# Robo2.net
KiCad netlist of a schematic drawn in Altium Designer
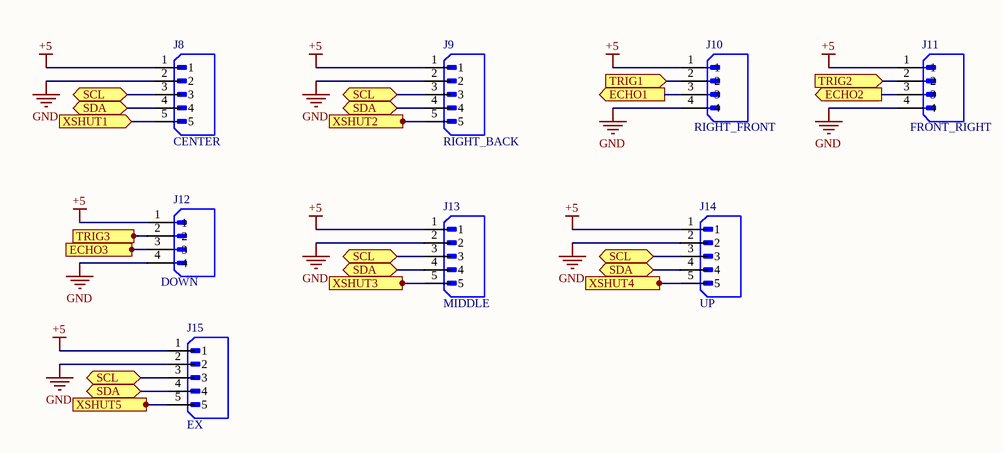
[diagram p0: Robo2.SchDoc]

(export (version "E")
  (design (tool "Eeschema 10.0.6"))
  (components
    (comp (ref "J8")
      (value "CENTER")
      (footprint "JST_B5B-XH-A(LF)(SN)")
      (description "Connector Header Through Hole 5 position 0.098 (2.50mm)")
      (fields (field (name "MF") "JST Sales America Inc.") (field (name "MP") "B5B-XH-A(LF)(SN)"))
      (libsource (lib "robo") (part "B5B-XH-A(LF)(SN)"))
    )
    (comp (ref "J9")
      (value "RIGHT_BACK")
      (footprint "JST_B5B-XH-A(LF)(SN)")
      (description "Connector Header Through Hole 5 position 0.098 (2.50mm)")
      (fields (field (name "MF") "JST Sales America Inc.") (field (name "MP") "B5B-XH-A(LF)(SN)"))
      (libsource (lib "robo") (part "B5B-XH-A(LF)(SN)"))
    )
    (comp (ref "J10")
      (value "RIGHT_FRONT")
      (footprint "JST_B4B-XH-A(LF)(SN)")
      (description "Connector Header Through Hole 4 position 0.098 (2.50mm)")
      (fields (field (name "MP") "B4B-XH-A(LF)(SN)") (field (name "MF") "JST Sales"))
      (libsource (lib "robo") (part "B4B-XH-A(LF)(SN)"))
    )
    (comp (ref "J11")
      (value "FRONT_RIGHT")
      (footprint "JST_B4B-XH-A(LF)(SN)")
      (description "Connector Header Through Hole 4 position 0.098 (2.50mm)")
      (fields (field (name "MP") "B4B-XH-A(LF)(SN)") (field (name "MF") "JST Sales"))
      (libsource (lib "robo") (part "B4B-XH-A(LF)(SN)"))
    )
    (comp (ref "J12")
      (value "DOWN")
      (footprint "JST_B4B-XH-A(LF)(SN)")
      (description "Connector Header Through Hole 4 position 0.098 (2.50mm)")
      (fields (field (name "MP") "B4B-XH-A(LF)(SN)") (field (name "MF") "JST Sales"))
      (libsource (lib "robo") (part "B4B-XH-A(LF)(SN)"))
    )
    (comp (ref "J13")
      (value "MIDDLE")
      (footprint "JST_B5B-XH-A(LF)(SN)")
      (description "Connector Header Through Hole 5 position 0.098 (2.50mm)")
      (fields (field (name "MF") "JST Sales America Inc.") (field (name "MP") "B5B-XH-A(LF)(SN)"))
      (libsource (lib "robo") (part "B5B-XH-A(LF)(SN)"))
    )
    (comp (ref "J14")
      (value "UP")
      (footprint "JST_B5B-XH-A(LF)(SN)")
      (description "Connector Header Through Hole 5 position 0.098 (2.50mm)")
      (fields (field (name "MF") "JST Sales America Inc.") (field (name "MP") "B5B-XH-A(LF)(SN)"))
      (libsource (lib "robo") (part "B5B-XH-A(LF)(SN)"))
    )
    (comp (ref "J15")
      (value "EX")
      (footprint "JST_B5B-XH-A(LF)(SN)")
      (description "Connector Header Through Hole 5 position 0.098 (2.50mm)")
      (fields (field (name "MF") "JST Sales America Inc.") (field (name "MP") "B5B-XH-A(LF)(SN)"))
      (libsource (lib "robo") (part "B5B-XH-A(LF)(SN)"))
    )
  )
  (nets
    (net (code "1") (name "+5") (class "Default")
      (node (ref "J10") (pin "1") (pinfunction "1_1") (pintype "passive"))
      (node (ref "J11") (pin "1") (pinfunction "1_1") (pintype "passive"))
      (node (ref "J12") (pin "1") (pinfunction "1_1") (pintype "passive"))
      (node (ref "J13") (pin "1") (pinfunction "1_1") (pintype "passive"))
      (node (ref "J14") (pin "1") (pinfunction "1_1") (pintype "passive"))
      (node (ref "J15") (pin "1") (pinfunction "1_1") (pintype "passive"))
      (node (ref "J8") (pin "1") (pinfunction "1_1") (pintype "passive"))
      (node (ref "J9") (pin "1") (pinfunction "1_1") (pintype "passive"))
    )
    (net (code "2") (name "/ECHO1") (class "Default")
      (node (ref "J10") (pin "3") (pinfunction "3_3") (pintype "passive"))
    )
    (net (code "3") (name "/ECHO2") (class "Default")
      (node (ref "J11") (pin "3") (pinfunction "3_3") (pintype "passive"))
    )
    (net (code "4") (name "/ECHO3") (class "Default")
      (node (ref "J12") (pin "3") (pinfunction "3_3") (pintype "passive"))
    )
    (net (code "5") (name "/SCL") (class "Default")
      (node (ref "J13") (pin "3") (pinfunction "3_3") (pintype "passive"))
      (node (ref "J14") (pin "3") (pinfunction "3_3") (pintype "passive"))
      (node (ref "J15") (pin "3") (pinfunction "3_3") (pintype "passive"))
      (node (ref "J8") (pin "3") (pinfunction "3_3") (pintype "passive"))
      (node (ref "J9") (pin "3") (pinfunction "3_3") (pintype "passive"))
    )
    (net (code "6") (name "/SDA") (class "Default")
      (node (ref "J13") (pin "4") (pinfunction "4_4") (pintype "passive"))
      (node (ref "J14") (pin "4") (pinfunction "4_4") (pintype "passive"))
      (node (ref "J15") (pin "4") (pinfunction "4_4") (pintype "passive"))
      (node (ref "J8") (pin "4") (pinfunction "4_4") (pintype "passive"))
      (node (ref "J9") (pin "4") (pinfunction "4_4") (pintype "passive"))
    )
    (net (code "7") (name "/TRIG1") (class "Default")
      (node (ref "J10") (pin "2") (pinfunction "2_2") (pintype "passive"))
    )
    (net (code "8") (name "/TRIG2") (class "Default")
      (node (ref "J11") (pin "2") (pinfunction "2_2") (pintype "passive"))
    )
    (net (code "9") (name "/TRIG3") (class "Default")
      (node (ref "J12") (pin "2") (pinfunction "2_2") (pintype "passive"))
    )
    (net (code "10") (name "/XSHUT1") (class "Default")
      (node (ref "J8") (pin "5") (pinfunction "5_5") (pintype "passive"))
    )
    (net (code "11") (name "/XSHUT2") (class "Default")
      (node (ref "J9") (pin "5") (pinfunction "5_5") (pintype "passive"))
    )
    (net (code "12") (name "/XSHUT3") (class "Default")
      (node (ref "J13") (pin "5") (pinfunction "5_5") (pintype "passive"))
    )
    (net (code "13") (name "/XSHUT4") (class "Default")
      (node (ref "J14") (pin "5") (pinfunction "5_5") (pintype "passive"))
    )
    (net (code "14") (name "/XSHUT5") (class "Default")
      (node (ref "J15") (pin "5") (pinfunction "5_5") (pintype "passive"))
    )
    (net (code "15") (name "GND") (class "Default")
      (node (ref "J10") (pin "4") (pinfunction "4_4") (pintype "passive"))
      (node (ref "J11") (pin "4") (pinfunction "4_4") (pintype "passive"))
      (node (ref "J12") (pin "4") (pinfunction "4_4") (pintype "passive"))
      (node (ref "J13") (pin "2") (pinfunction "2_2") (pintype "passive"))
      (node (ref "J14") (pin "2") (pinfunction "2_2") (pintype "passive"))
      (node (ref "J15") (pin "2") (pinfunction "2_2") (pintype "passive"))
      (node (ref "J8") (pin "2") (pinfunction "2_2") (pintype "passive"))
      (node (ref "J9") (pin "2") (pinfunction "2_2") (pintype "passive"))
    )
  )
)
